# Keys.net
KiCad netlist of a schematic drawn in Altium Designer
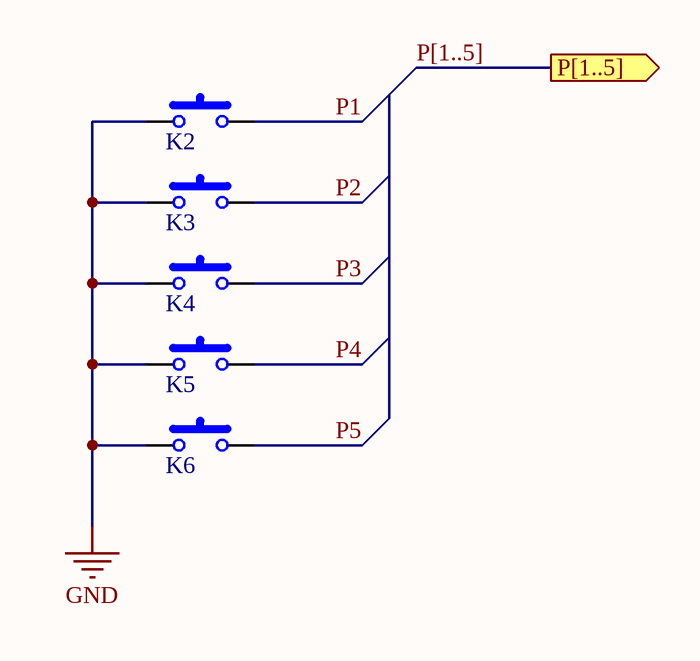
[diagram p0: Keys.SchDoc]

(export (version "E")
  (design (tool "Eeschema 10.0.6"))
  (components
    (comp (ref "K2")
      (value "KEY")
      (footprint "TACK6")
      (description "Switch")
      (fields (field (name "PUBLISHER") "Altium Limited"))
      (libsource (lib "TEST2024") (part "KEY"))
    )
    (comp (ref "K3")
      (value "KEY")
      (footprint "TACK6")
      (description "Switch")
      (fields (field (name "PUBLISHER") "Altium Limited"))
      (libsource (lib "TEST2024") (part "KEY"))
    )
    (comp (ref "K4")
      (value "KEY")
      (footprint "TACK6")
      (description "Switch")
      (fields (field (name "PUBLISHER") "Altium Limited"))
      (libsource (lib "TEST2024") (part "KEY"))
    )
    (comp (ref "K5")
      (value "KEY")
      (footprint "TACK6")
      (description "Switch")
      (fields (field (name "PUBLISHER") "Altium Limited"))
      (libsource (lib "TEST2024") (part "KEY"))
    )
    (comp (ref "K6")
      (value "KEY")
      (footprint "TACK6")
      (description "Switch")
      (fields (field (name "PUBLISHER") "Altium Limited"))
      (libsource (lib "TEST2024") (part "KEY"))
    )
  )
  (nets
    (net (code "1") (name "/P1") (class "Default")
      (node (ref "K2") (pin "2") (pinfunction "2_2") (pintype "passive"))
    )
    (net (code "2") (name "/P2") (class "Default")
      (node (ref "K3") (pin "2") (pinfunction "2_2") (pintype "passive"))
    )
    (net (code "3") (name "/P3") (class "Default")
      (node (ref "K4") (pin "2") (pinfunction "2_2") (pintype "passive"))
    )
    (net (code "4") (name "/P4") (class "Default")
      (node (ref "K5") (pin "2") (pinfunction "2_2") (pintype "passive"))
    )
    (net (code "5") (name "/P5") (class "Default")
      (node (ref "K6") (pin "2") (pinfunction "2_2") (pintype "passive"))
    )
    (net (code "7") (name "GND") (class "Default")
      (node (ref "K2") (pin "1") (pinfunction "1_1") (pintype "passive"))
      (node (ref "K3") (pin "1") (pinfunction "1_1") (pintype "passive"))
      (node (ref "K4") (pin "1") (pinfunction "1_1") (pintype "passive"))
      (node (ref "K5") (pin "1") (pinfunction "1_1") (pintype "passive"))
      (node (ref "K6") (pin "1") (pinfunction "1_1") (pintype "passive"))
    )
  )
)
